# weatherstation.net
KiCad netlist of a schematic drawn in EAGLE
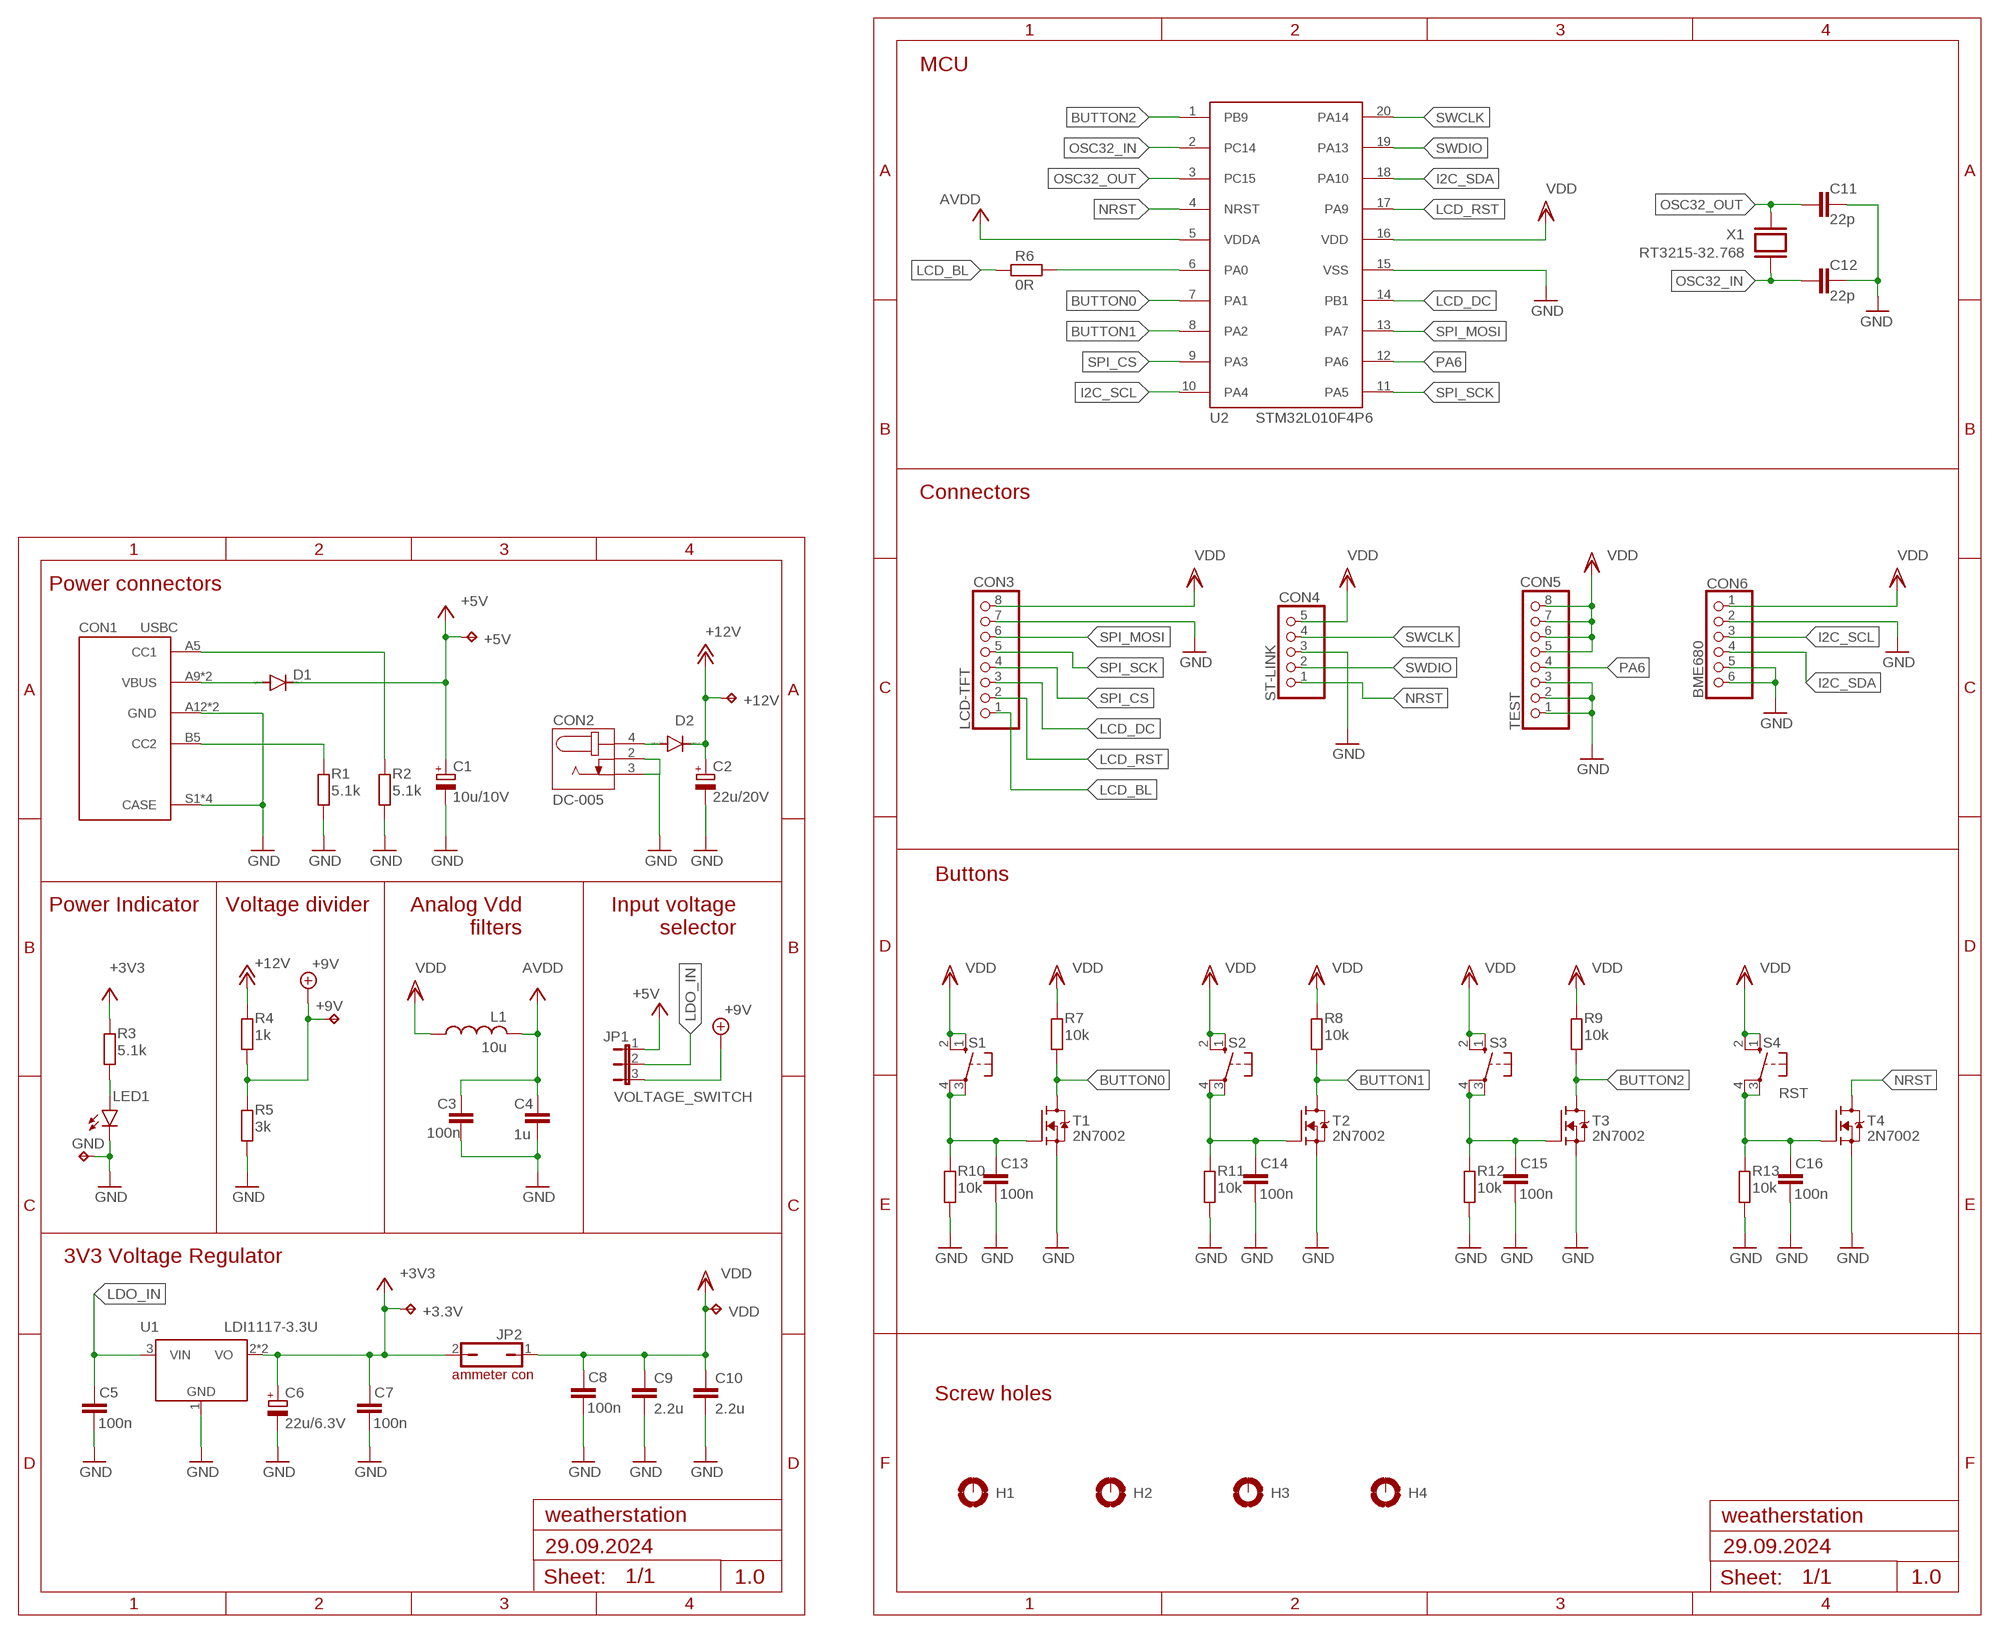
[diagram p0: schematic, sheet 1]

(export (version "E")
  (design (tool "Eeschema 10.0.6"))
  (components
    (comp (ref "+3.3V")
      (value "TPPAD1-13")
      (footprint "eagle-import:P1-13")
      (libsource (lib "eagle-import") (part "TPPAD1-13"))
    )
    (comp (ref "+5V")
      (value "TPPAD1-13")
      (footprint "eagle-import:P1-13")
      (libsource (lib "eagle-import") (part "TPPAD1-13"))
    )
    (comp (ref "+9V")
      (value "TPPAD1-13")
      (footprint "eagle-import:P1-13")
      (libsource (lib "eagle-import") (part "TPPAD1-13"))
    )
    (comp (ref "+12V")
      (value "TPPAD1-13")
      (footprint "eagle-import:P1-13")
      (libsource (lib "eagle-import") (part "TPPAD1-13"))
    )
    (comp (ref "C1")
      (value "10u/10V")
      (footprint "eagle-import:A_3216-18R")
      (libsource (lib "eagle-import") (part "CPOL-EUA/3216-18R"))
    )
    (comp (ref "C2")
      (value "22u/20V")
      (footprint "eagle-import:C_6032-28R")
      (libsource (lib "eagle-import") (part "CPOL-EUC/6032-28R"))
    )
    (comp (ref "C3")
      (value "100n")
      (footprint "eagle-import:C0603K")
      (libsource (lib "eagle-import") (part "C-EUC0603K"))
    )
    (comp (ref "C4")
      (value "1u")
      (footprint "eagle-import:C0603K")
      (libsource (lib "eagle-import") (part "C-EUC0603K"))
    )
    (comp (ref "C5")
      (value "100n")
      (footprint "eagle-import:C0603K")
      (libsource (lib "eagle-import") (part "C-EUC0603K"))
    )
    (comp (ref "C6")
      (value "22u/6.3V")
      (footprint "eagle-import:A_3216-18R")
      (libsource (lib "eagle-import") (part "CPOL-EUA/3216-18R"))
    )
    (comp (ref "C7")
      (value "100n")
      (footprint "eagle-import:C0603K")
      (libsource (lib "eagle-import") (part "C-EUC0603K"))
    )
    (comp (ref "C8")
      (value "100n")
      (footprint "eagle-import:C0603K")
      (libsource (lib "eagle-import") (part "C-EUC0603K"))
    )
    (comp (ref "C9")
      (value "2.2u")
      (footprint "eagle-import:C0805")
      (libsource (lib "eagle-import") (part "C-EUC0805"))
    )
    (comp (ref "C10")
      (value "2.2u")
      (footprint "eagle-import:C0805")
      (libsource (lib "eagle-import") (part "C-EUC0805"))
    )
    (comp (ref "C11")
      (value "22p")
      (footprint "eagle-import:C0603K")
      (libsource (lib "eagle-import") (part "C-EUC0603K"))
    )
    (comp (ref "C12")
      (value "22p")
      (footprint "eagle-import:C0603K")
      (libsource (lib "eagle-import") (part "C-EUC0603K"))
    )
    (comp (ref "C13")
      (value "100n")
      (footprint "eagle-import:C0603K")
      (libsource (lib "eagle-import") (part "C-EUC0603K"))
    )
    (comp (ref "C14")
      (value "100n")
      (footprint "eagle-import:C0603K")
      (libsource (lib "eagle-import") (part "C-EUC0603K"))
    )
    (comp (ref "C15")
      (value "100n")
      (footprint "eagle-import:C0603K")
      (libsource (lib "eagle-import") (part "C-EUC0603K"))
    )
    (comp (ref "C16")
      (value "100n")
      (footprint "eagle-import:C0603K")
      (libsource (lib "eagle-import") (part "C-EUC0603K"))
    )
    (comp (ref "CON1")
      (value "USBC")
      (footprint "eagle-import:CUI_UJC-HP-3-SMT-TR")
      (libsource (lib "eagle-import") (part "USBC"))
    )
    (comp (ref "CON2")
      (value "DC-005")
      (footprint "eagle-import:NINIGI_DC-005")
      (fields (field (name "MF") "Best Inc."))
      (libsource (lib "eagle-import") (part "DC-005"))
    )
    (comp (ref "CON3")
      (value "LCD-TFT")
      (footprint "eagle-import:LCD")
      (libsource (lib "eagle-import") (part "LCD-TFT"))
    )
    (comp (ref "CON4")
      (value "ST-LINK")
      (footprint "eagle-import:1X05")
      (libsource (lib "eagle-import") (part "PINHD-1X5"))
    )
    (comp (ref "CON5")
      (value "TEST")
      (footprint "eagle-import:1X08")
      (libsource (lib "eagle-import") (part "PINHD-1X8"))
    )
    (comp (ref "CON6")
      (value "BME680")
      (footprint "eagle-import:BME680")
      (libsource (lib "eagle-import") (part "BME680"))
    )
    (comp (ref "D1")
      (value "CGRM4001-G")
      (footprint "eagle-import:SOD-123_MINI-SMA")
      (libsource (lib "eagle-import") (part "CGRM400-G1"))
    )
    (comp (ref "D2")
      (value "ES2D")
      (footprint "eagle-import:SMB")
      (libsource (lib "eagle-import") (part "ES2D"))
    )
    (comp (ref "GND")
      (value "TPPAD1-13")
      (footprint "eagle-import:P1-13")
      (libsource (lib "eagle-import") (part "TPPAD1-13"))
    )
    (comp (ref "H1")
      (value "MOUNT-PAD-ROUND2.8")
      (footprint "eagle-import:2,8-PAD")
      (libsource (lib "eagle-import") (part "MOUNT-PAD-ROUND2.8"))
    )
    (comp (ref "H2")
      (value "MOUNT-PAD-ROUND2.8")
      (footprint "eagle-import:2,8-PAD")
      (libsource (lib "eagle-import") (part "MOUNT-PAD-ROUND2.8"))
    )
    (comp (ref "H3")
      (value "MOUNT-PAD-ROUND2.8")
      (footprint "eagle-import:2,8-PAD")
      (libsource (lib "eagle-import") (part "MOUNT-PAD-ROUND2.8"))
    )
    (comp (ref "H4")
      (value "MOUNT-PAD-ROUND2.8")
      (footprint "eagle-import:2,8-PAD")
      (libsource (lib "eagle-import") (part "MOUNT-PAD-ROUND2.8"))
    )
    (comp (ref "JP1")
      (value "VOLTAGE_SWITCH")
      (footprint "eagle-import:JP2")
      (libsource (lib "eagle-import") (part "VOLTAGE_SWITCH"))
    )
    (comp (ref "JP2")
      (value "JP1Q")
      (footprint "eagle-import:JP1")
      (libsource (lib "eagle-import") (part "JP1Q"))
    )
    (comp (ref "L1")
      (value "10u")
      (footprint "eagle-import:L2012C")
      (libsource (lib "eagle-import") (part "L-USL2012C"))
    )
    (comp (ref "LED1")
      (value "LEDCHIPLED_1206")
      (footprint "eagle-import:CHIPLED_1206")
      (libsource (lib "eagle-import") (part "LEDCHIPLED_1206"))
    )
    (comp (ref "R1")
      (value "5.1k")
      (footprint "eagle-import:R0805")
      (libsource (lib "eagle-import") (part "R-EU_R0805"))
    )
    (comp (ref "R2")
      (value "5.1k")
      (footprint "eagle-import:R0805")
      (libsource (lib "eagle-import") (part "R-EU_R0805"))
    )
    (comp (ref "R3")
      (value "5.1k")
      (footprint "eagle-import:R0805")
      (libsource (lib "eagle-import") (part "R-EU_R0805"))
    )
    (comp (ref "R4")
      (value "1k")
      (footprint "eagle-import:R0805")
      (libsource (lib "eagle-import") (part "R-EU_R0805"))
    )
    (comp (ref "R5")
      (value "3k")
      (footprint "eagle-import:R0805")
      (libsource (lib "eagle-import") (part "R-EU_R0805"))
    )
    (comp (ref "R6")
      (value "0R")
      (footprint "eagle-import:R0805")
      (libsource (lib "eagle-import") (part "R-EU_R0805"))
    )
    (comp (ref "R7")
      (value "10k")
      (footprint "eagle-import:R0805")
      (libsource (lib "eagle-import") (part "R-EU_R0805"))
    )
    (comp (ref "R8")
      (value "10k")
      (footprint "eagle-import:R0805")
      (libsource (lib "eagle-import") (part "R-EU_R0805"))
    )
    (comp (ref "R9")
      (value "10k")
      (footprint "eagle-import:R0805")
      (libsource (lib "eagle-import") (part "R-EU_R0805"))
    )
    (comp (ref "R10")
      (value "10k")
      (footprint "eagle-import:R0805")
      (libsource (lib "eagle-import") (part "R-EU_R0805"))
    )
    (comp (ref "R11")
      (value "10k")
      (footprint "eagle-import:R0805")
      (libsource (lib "eagle-import") (part "R-EU_R0805"))
    )
    (comp (ref "R12")
      (value "10k")
      (footprint "eagle-import:R0805")
      (libsource (lib "eagle-import") (part "R-EU_R0805"))
    )
    (comp (ref "R13")
      (value "10k")
      (footprint "eagle-import:R0805")
      (libsource (lib "eagle-import") (part "R-EU_R0805"))
    )
    (comp (ref "S1")
      (value "BUTTON0")
      (footprint "eagle-import:B3F-10XX")
      (fields (field (name "MPN") "B3F-1000"))
      (libsource (lib "eagle-import") (part "10-XX"))
    )
    (comp (ref "S2")
      (value "BUTTON1")
      (footprint "eagle-import:B3F-10XX")
      (fields (field (name "MPN") "B3F-1000"))
      (libsource (lib "eagle-import") (part "10-XX"))
    )
    (comp (ref "S3")
      (value "BUTTON2")
      (footprint "eagle-import:B3F-10XX")
      (fields (field (name "MPN") "B3F-1000"))
      (libsource (lib "eagle-import") (part "10-XX"))
    )
    (comp (ref "S4")
      (value "RST")
      (footprint "eagle-import:B3F-10XX")
      (fields (field (name "MPN") "B3F-1000"))
      (libsource (lib "eagle-import") (part "10-XX"))
    )
    (comp (ref "T1")
      (value "2N7002")
      (footprint "eagle-import:SOT95P240X111-3N")
      (libsource (lib "eagle-import") (part "2N7002"))
    )
    (comp (ref "T2")
      (value "2N7002")
      (footprint "eagle-import:SOT95P240X111-3N")
      (libsource (lib "eagle-import") (part "2N7002"))
    )
    (comp (ref "T3")
      (value "2N7002")
      (footprint "eagle-import:SOT95P240X111-3N")
      (libsource (lib "eagle-import") (part "2N7002"))
    )
    (comp (ref "T4")
      (value "2N7002")
      (footprint "eagle-import:SOT95P240X111-3N")
      (libsource (lib "eagle-import") (part "2N7002"))
    )
    (comp (ref "U1")
      (value "LDI1117-3.3U")
      (footprint "eagle-import:SOT89")
      (libsource (lib "eagle-import") (part "LDI1117-3.3U"))
    )
    (comp (ref "U2")
      (value "STM32L010F4P6")
      (footprint "eagle-import:TSSOP20")
      (libsource (lib "eagle-import") (part "STM32L010F4P6"))
    )
    (comp (ref "VDD")
      (value "TPPAD1-13")
      (footprint "eagle-import:P1-13")
      (libsource (lib "eagle-import") (part "TPPAD1-13"))
    )
    (comp (ref "X1")
      (value "RT3215-32.768")
      (footprint "eagle-import:XTAL_RT3215-32.768-12.5-TR")
      (libsource (lib "eagle-import") (part "RT3215-32.768"))
    )
  )
  (nets
    (net (code "1") (name "+3V3") (class "Default")
      (node (ref "+3.3V") (pin "TP") (pinfunction "TP_TP") (pintype "input"))
      (node (ref "C6") (pin "+") (pinfunction "+_+") (pintype "passive"))
      (node (ref "C7") (pin "1") (pinfunction "1_1") (pintype "passive"))
      (node (ref "JP2") (pin "2") (pinfunction "2_2") (pintype "passive"))
      (node (ref "R3") (pin "2") (pinfunction "2_2") (pintype "passive"))
      (node (ref "U1") (pin "2") (pinfunction "VO_2") (pintype "output"))
      (node (ref "U1") (pin "2@1") (pinfunction "VO_2@1") (pintype "output"))
    )
    (net (code "2") (name "+5V") (class "Default")
      (node (ref "+5V") (pin "TP") (pinfunction "TP_TP") (pintype "input"))
      (node (ref "C1") (pin "+") (pinfunction "+_+") (pintype "passive"))
      (node (ref "D1") (pin "C") (pinfunction "C_C") (pintype "passive"))
      (node (ref "JP1") (pin "1") (pinfunction "1_1") (pintype "passive"))
    )
    (net (code "3") (name "+9V") (class "Default")
      (node (ref "+9V") (pin "TP") (pinfunction "TP_TP") (pintype "input"))
      (node (ref "JP1") (pin "3") (pinfunction "3_3") (pintype "passive"))
      (node (ref "R4") (pin "2") (pinfunction "2_2") (pintype "passive"))
      (node (ref "R5") (pin "1") (pinfunction "1_1") (pintype "passive"))
    )
    (net (code "4") (name "+12V") (class "Default")
      (node (ref "+12V") (pin "TP") (pinfunction "TP_TP") (pintype "input"))
      (node (ref "C2") (pin "+") (pinfunction "+_+") (pintype "passive"))
      (node (ref "D2") (pin "C") (pinfunction "C_C") (pintype "passive"))
      (node (ref "R4") (pin "1") (pinfunction "1_1") (pintype "passive"))
    )
    (net (code "5") (name "AVDD") (class "Default")
      (node (ref "C3") (pin "2") (pinfunction "2_2") (pintype "passive"))
      (node (ref "C4") (pin "1") (pinfunction "1_1") (pintype "passive"))
      (node (ref "L1") (pin "2") (pinfunction "2_2") (pintype "passive"))
      (node (ref "U2") (pin "5") (pinfunction "VDDA_5") (pintype "power_in"))
    )
    (net (code "6") (name "BUTTON0") (class "Default")
      (node (ref "R7") (pin "1") (pinfunction "1_1") (pintype "passive"))
      (node (ref "T1") (pin "3") (pinfunction "D_3") (pintype "passive"))
      (node (ref "U2") (pin "7") (pinfunction "PA1_7") (pintype "bidirectional"))
    )
    (net (code "7") (name "BUTTON1") (class "Default")
      (node (ref "R8") (pin "1") (pinfunction "1_1") (pintype "passive"))
      (node (ref "T2") (pin "3") (pinfunction "D_3") (pintype "passive"))
      (node (ref "U2") (pin "8") (pinfunction "PA2_8") (pintype "bidirectional"))
    )
    (net (code "8") (name "BUTTON2") (class "Default")
      (node (ref "R9") (pin "1") (pinfunction "1_1") (pintype "passive"))
      (node (ref "T3") (pin "3") (pinfunction "D_3") (pintype "passive"))
      (node (ref "U2") (pin "1") (pinfunction "PB9_1") (pintype "bidirectional"))
    )
    (net (code "9") (name "GND") (class "Default")
      (node (ref "C1") (pin "-") (pinfunction "-_-") (pintype "passive"))
      (node (ref "C10") (pin "2") (pinfunction "2_2") (pintype "passive"))
      (node (ref "C11") (pin "1") (pinfunction "1_1") (pintype "passive"))
      (node (ref "C12") (pin "1") (pinfunction "1_1") (pintype "passive"))
      (node (ref "C13") (pin "2") (pinfunction "2_2") (pintype "passive"))
      (node (ref "C14") (pin "2") (pinfunction "2_2") (pintype "passive"))
      (node (ref "C15") (pin "2") (pinfunction "2_2") (pintype "passive"))
      (node (ref "C16") (pin "2") (pinfunction "2_2") (pintype "passive"))
      (node (ref "C2") (pin "-") (pinfunction "-_-") (pintype "passive"))
      (node (ref "C3") (pin "1") (pinfunction "1_1") (pintype "passive"))
      (node (ref "C4") (pin "2") (pinfunction "2_2") (pintype "passive"))
      (node (ref "C5") (pin "2") (pinfunction "2_2") (pintype "passive"))
      (node (ref "C6") (pin "-") (pinfunction "-_-") (pintype "passive"))
      (node (ref "C7") (pin "2") (pinfunction "2_2") (pintype "passive"))
      (node (ref "C8") (pin "2") (pinfunction "2_2") (pintype "passive"))
      (node (ref "C9") (pin "2") (pinfunction "2_2") (pintype "passive"))
      (node (ref "CON1") (pin "A12") (pinfunction "GND_A12") (pintype "power_in"))
      (node (ref "CON1") (pin "B12") (pinfunction "GND_B12") (pintype "power_in"))
      (node (ref "CON1") (pin "S1") (pinfunction "CASE_S1") (pintype "power_in"))
      (node (ref "CON1") (pin "S2") (pinfunction "CASE_S2") (pintype "power_in"))
      (node (ref "CON1") (pin "S3") (pinfunction "CASE_S3") (pintype "power_in"))
      (node (ref "CON1") (pin "S4") (pinfunction "CASE_S4") (pintype "power_in"))
      (node (ref "CON2") (pin "2") (pinfunction "4_2") (pintype "passive"))
      (node (ref "CON2") (pin "3") (pinfunction "5_3") (pintype "passive"))
      (node (ref "CON3") (pin "7") (pinfunction "GND_7") (pintype "power_in"))
      (node (ref "CON4") (pin "3") (pinfunction "3_3") (pintype "passive"))
      (node (ref "CON5") (pin "1") (pinfunction "1_1") (pintype "passive"))
      (node (ref "CON5") (pin "2") (pinfunction "2_2") (pintype "passive"))
      (node (ref "CON5") (pin "3") (pinfunction "3_3") (pintype "passive"))
      (node (ref "CON6") (pin "2") (pinfunction "GND_2") (pintype "power_in"))
      (node (ref "CON6") (pin "5") (pinfunction "SDO_5") (pintype "bidirectional"))
      (node (ref "CON6") (pin "6") (pinfunction "CS_6") (pintype "bidirectional"))
      (node (ref "GND") (pin "TP") (pinfunction "TP_TP") (pintype "input"))
      (node (ref "LED1") (pin "C") (pinfunction "C_C") (pintype "passive"))
      (node (ref "R1") (pin "2") (pinfunction "2_2") (pintype "passive"))
      (node (ref "R10") (pin "1") (pinfunction "1_1") (pintype "passive"))
      (node (ref "R11") (pin "1") (pinfunction "1_1") (pintype "passive"))
      (node (ref "R12") (pin "1") (pinfunction "1_1") (pintype "passive"))
      (node (ref "R13") (pin "1") (pinfunction "1_1") (pintype "passive"))
      (node (ref "R2") (pin "1") (pinfunction "1_1") (pintype "passive"))
      (node (ref "R5") (pin "2") (pinfunction "2_2") (pintype "passive"))
      (node (ref "T1") (pin "2") (pinfunction "S_2") (pintype "passive"))
      (node (ref "T2") (pin "2") (pinfunction "S_2") (pintype "passive"))
      (node (ref "T3") (pin "2") (pinfunction "S_2") (pintype "passive"))
      (node (ref "T4") (pin "2") (pinfunction "S_2") (pintype "passive"))
      (node (ref "U1") (pin "1") (pinfunction "GND_1") (pintype "power_in"))
      (node (ref "U2") (pin "15") (pinfunction "VSS_15") (pintype "power_in"))
    )
    (net (code "10") (name "I2C_SCL") (class "Default")
      (node (ref "CON6") (pin "3") (pinfunction "SCL_3") (pintype "bidirectional"))
      (node (ref "U2") (pin "10") (pinfunction "PA4_10") (pintype "bidirectional"))
    )
    (net (code "11") (name "I2C_SDA") (class "Default")
      (node (ref "CON6") (pin "4") (pinfunction "SDA_4") (pintype "bidirectional"))
      (node (ref "U2") (pin "18") (pinfunction "PA10_18") (pintype "bidirectional"))
    )
    (net (code "12") (name "LCD_BL") (class "Default")
      (node (ref "CON3") (pin "1") (pinfunction "BL_1") (pintype "bidirectional"))
      (node (ref "R6") (pin "1") (pinfunction "1_1") (pintype "passive"))
    )
    (net (code "13") (name "LCD_DC") (class "Default")
      (node (ref "CON3") (pin "3") (pinfunction "DC_3") (pintype "bidirectional"))
      (node (ref "U2") (pin "14") (pinfunction "PB1_14") (pintype "bidirectional"))
    )
    (net (code "14") (name "LCD_RST") (class "Default")
      (node (ref "CON3") (pin "2") (pinfunction "RST_2") (pintype "bidirectional"))
      (node (ref "U2") (pin "17") (pinfunction "PA9_17") (pintype "bidirectional"))
    )
    (net (code "15") (name "LDO_IN") (class "Default")
      (node (ref "C5") (pin "1") (pinfunction "1_1") (pintype "passive"))
      (node (ref "JP1") (pin "2") (pinfunction "2_2") (pintype "passive"))
      (node (ref "U1") (pin "3") (pinfunction "VIN_3") (pintype "input"))
    )
    (net (code "16") (name "NRST") (class "Default")
      (node (ref "CON4") (pin "1") (pinfunction "1_1") (pintype "passive"))
      (node (ref "T4") (pin "3") (pinfunction "D_3") (pintype "passive"))
      (node (ref "U2") (pin "4") (pinfunction "NRST_4") (pintype "bidirectional"))
    )
    (net (code "17") (name "Net-(CON1-CC1)") (class "Default")
      (node (ref "CON1") (pin "A5") (pinfunction "CC1_A5") (pintype "bidirectional"))
      (node (ref "R2") (pin "2") (pinfunction "2_2") (pintype "passive"))
    )
    (net (code "18") (name "Net-(CON1-CC2)") (class "Default")
      (node (ref "CON1") (pin "B5") (pinfunction "CC2_B5") (pintype "bidirectional"))
      (node (ref "R1") (pin "1") (pinfunction "1_1") (pintype "passive"))
    )
    (net (code "19") (name "Net-(CON1-VBUS-PadA9)") (class "Default")
      (node (ref "CON1") (pin "A9") (pinfunction "VBUS_A9") (pintype "power_in"))
      (node (ref "CON1") (pin "B9") (pinfunction "VBUS_B9") (pintype "power_in"))
      (node (ref "D1") (pin "A") (pinfunction "A_A") (pintype "passive"))
    )
    (net (code "20") (name "Net-(CON2-2)") (class "Default")
      (node (ref "CON2") (pin "4") (pinfunction "2_4") (pintype "passive"))
      (node (ref "D2") (pin "A") (pinfunction "A_A") (pintype "passive"))
    )
    (net (code "21") (name "Net-(LED1-PadA)") (class "Default")
      (node (ref "LED1") (pin "A") (pinfunction "A_A") (pintype "passive"))
      (node (ref "R3") (pin "1") (pinfunction "1_1") (pintype "passive"))
    )
    (net (code "22") (name "Net-(S1-P)") (class "Default")
      (node (ref "C13") (pin "1") (pinfunction "1_1") (pintype "passive"))
      (node (ref "R10") (pin "2") (pinfunction "2_2") (pintype "passive"))
      (node (ref "S1") (pin "3") (pinfunction "P_3") (pintype "passive"))
      (node (ref "S1") (pin "4") (pinfunction "P1_4") (pintype "passive"))
      (node (ref "T1") (pin "1") (pinfunction "G_1") (pintype "passive"))
    )
    (net (code "23") (name "Net-(S2-P)") (class "Default")
      (node (ref "C14") (pin "1") (pinfunction "1_1") (pintype "passive"))
      (node (ref "R11") (pin "2") (pinfunction "2_2") (pintype "passive"))
      (node (ref "S2") (pin "3") (pinfunction "P_3") (pintype "passive"))
      (node (ref "S2") (pin "4") (pinfunction "P1_4") (pintype "passive"))
      (node (ref "T2") (pin "1") (pinfunction "G_1") (pintype "passive"))
    )
    (net (code "24") (name "Net-(S3-P)") (class "Default")
      (node (ref "C15") (pin "1") (pinfunction "1_1") (pintype "passive"))
      (node (ref "R12") (pin "2") (pinfunction "2_2") (pintype "passive"))
      (node (ref "S3") (pin "3") (pinfunction "P_3") (pintype "passive"))
      (node (ref "S3") (pin "4") (pinfunction "P1_4") (pintype "passive"))
      (node (ref "T3") (pin "1") (pinfunction "G_1") (pintype "passive"))
    )
    (net (code "25") (name "Net-(S4-P)") (class "Default")
      (node (ref "C16") (pin "1") (pinfunction "1_1") (pintype "passive"))
      (node (ref "R13") (pin "2") (pinfunction "2_2") (pintype "passive"))
      (node (ref "S4") (pin "3") (pinfunction "P_3") (pintype "passive"))
      (node (ref "S4") (pin "4") (pinfunction "P1_4") (pintype "passive"))
      (node (ref "T4") (pin "1") (pinfunction "G_1") (pintype "passive"))
    )
    (net (code "26") (name "Net-(U2-PA0)") (class "Default")
      (node (ref "R6") (pin "2") (pinfunction "2_2") (pintype "passive"))
      (node (ref "U2") (pin "6") (pinfunction "PA0_6") (pintype "bidirectional"))
    )
    (net (code "27") (name "OSC32_IN") (class "Default")
      (node (ref "C12") (pin "2") (pinfunction "2_2") (pintype "passive"))
      (node (ref "U2") (pin "2") (pinfunction "PC14_2") (pintype "bidirectional"))
      (node (ref "X1") (pin "2") (pinfunction "2_2") (pintype "passive"))
    )
    (net (code "28") (name "OSC32_OUT") (class "Default")
      (node (ref "C11") (pin "2") (pinfunction "2_2") (pintype "passive"))
      (node (ref "U2") (pin "3") (pinfunction "PC15_3") (pintype "bidirectional"))
      (node (ref "X1") (pin "1") (pinfunction "1_1") (pintype "passive"))
    )
    (net (code "29") (name "PA6") (class "Default")
      (node (ref "CON5") (pin "4") (pinfunction "4_4") (pintype "passive"))
      (node (ref "U2") (pin "12") (pinfunction "PA6_12") (pintype "bidirectional"))
    )
    (net (code "30") (name "SPI_CS") (class "Default")
      (node (ref "CON3") (pin "4") (pinfunction "CS_4") (pintype "bidirectional"))
      (node (ref "U2") (pin "9") (pinfunction "PA3_9") (pintype "bidirectional"))
    )
    (net (code "31") (name "SPI_MOSI") (class "Default")
      (node (ref "CON3") (pin "6") (pinfunction "DIN_6") (pintype "bidirectional"))
      (node (ref "U2") (pin "13") (pinfunction "PA7_13") (pintype "bidirectional"))
    )
    (net (code "32") (name "SPI_SCK") (class "Default")
      (node (ref "CON3") (pin "5") (pinfunction "CLK_5") (pintype "bidirectional"))
      (node (ref "U2") (pin "11") (pinfunction "PA5_11") (pintype "bidirectional"))
    )
    (net (code "33") (name "SWCLK") (class "Default")
      (node (ref "CON4") (pin "4") (pinfunction "4_4") (pintype "passive"))
      (node (ref "U2") (pin "20") (pinfunction "PA14_20") (pintype "bidirectional"))
    )
    (net (code "34") (name "SWDIO") (class "Default")
      (node (ref "CON4") (pin "2") (pinfunction "2_2") (pintype "passive"))
      (node (ref "U2") (pin "19") (pinfunction "PA13_19") (pintype "bidirectional"))
    )
    (net (code "35") (name "VDD") (class "Default")
      (node (ref "C10") (pin "1") (pinfunction "1_1") (pintype "passive"))
      (node (ref "C8") (pin "1") (pinfunction "1_1") (pintype "passive"))
      (node (ref "C9") (pin "1") (pinfunction "1_1") (pintype "passive"))
      (node (ref "CON3") (pin "8") (pinfunction "VCC_8") (pintype "bidirectional"))
      (node (ref "CON4") (pin "5") (pinfunction "5_5") (pintype "passive"))
      (node (ref "CON5") (pin "5") (pinfunction "5_5") (pintype "passive"))
      (node (ref "CON5") (pin "6") (pinfunction "6_6") (pintype "passive"))
      (node (ref "CON5") (pin "7") (pinfunction "7_7") (pintype "passive"))
      (node (ref "CON5") (pin "8") (pinfunction "8_8") (pintype "passive"))
      (node (ref "CON6") (pin "1") (pinfunction "VCC_1") (pintype "power_in"))
      (node (ref "JP2") (pin "1") (pinfunction "1_1") (pintype "passive"))
      (node (ref "L1") (pin "1") (pinfunction "1_1") (pintype "passive"))
      (node (ref "R7") (pin "2") (pinfunction "2_2") (pintype "passive"))
      (node (ref "R8") (pin "2") (pinfunction "2_2") (pintype "passive"))
      (node (ref "R9") (pin "2") (pinfunction "2_2") (pintype "passive"))
      (node (ref "S1") (pin "1") (pinfunction "S_1") (pintype "passive"))
      (node (ref "S1") (pin "2") (pinfunction "S1_2") (pintype "passive"))
      (node (ref "S2") (pin "1") (pinfunction "S_1") (pintype "passive"))
      (node (ref "S2") (pin "2") (pinfunction "S1_2") (pintype "passive"))
      (node (ref "S3") (pin "1") (pinfunction "S_1") (pintype "passive"))
      (node (ref "S3") (pin "2") (pinfunction "S1_2") (pintype "passive"))
      (node (ref "S4") (pin "1") (pinfunction "S_1") (pintype "passive"))
      (node (ref "S4") (pin "2") (pinfunction "S1_2") (pintype "passive"))
      (node (ref "U2") (pin "16") (pinfunction "VDD_16") (pintype "power_in"))
      (node (ref "VDD") (pin "TP") (pinfunction "TP_TP") (pintype "input"))
    )
    (net (code "36") (name "unconnected-(H1-MOUNT-PadB2,8)") (class "Default")
      (node (ref "H1") (pin "B2,8") (pinfunction "MOUNT_B2,8") (pintype "passive"))
    )
    (net (code "37") (name "unconnected-(H2-MOUNT-PadB2,8)") (class "Default")
      (node (ref "H2") (pin "B2,8") (pinfunction "MOUNT_B2,8") (pintype "passive"))
    )
    (net (code "38") (name "unconnected-(H3-MOUNT-PadB2,8)") (class "Default")
      (node (ref "H3") (pin "B2,8") (pinfunction "MOUNT_B2,8") (pintype "passive"))
    )
    (net (code "39") (name "unconnected-(H4-MOUNT-PadB2,8)") (class "Default")
      (node (ref "H4") (pin "B2,8") (pinfunction "MOUNT_B2,8") (pintype "passive"))
    )
  )
)
